# measure_temperature_sch.net
KiCad netlist of a schematic drawn in EAGLE
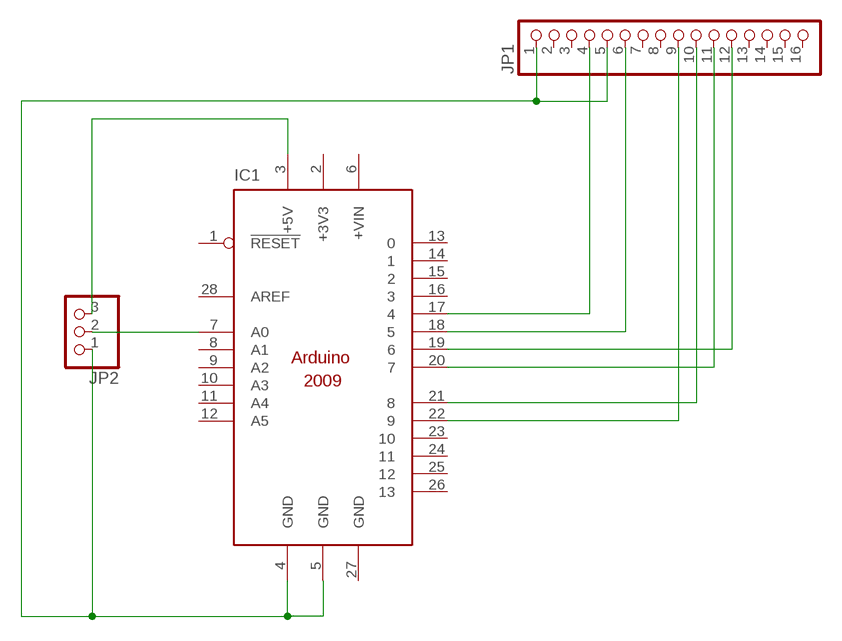
[diagram p0: schematic, sheet 1]

(export (version "E")
  (design (tool "Eeschema 10.0.6"))
  (components
    (comp (ref "IC1")
      (value "ARDUINO2009_12")
      (footprint "eagle-import:ARDUINO2009_2")
      (libsource (lib "eagle-import") (part "ARDUINO2009_12"))
    )
    (comp (ref "JP1")
      (value "PINHD-1X16")
      (footprint "eagle-import:1X16")
      (libsource (lib "eagle-import") (part "PINHD-1X16"))
    )
    (comp (ref "JP2")
      (value "PINHD-1X3")
      (footprint "eagle-import:1X03")
      (libsource (lib "eagle-import") (part "PINHD-1X3"))
    )
  )
  (nets
    (net (code "1") (name "/+3V3") (class "Default")
      (node (ref "IC1") (pin "2") (pinfunction "+3V3_2") (pintype "power_in"))
    )
    (net (code "2") (name "/GND") (class "Default")
      (node (ref "IC1") (pin "27") (pinfunction "GND_27") (pintype "power_in"))
    )
    (net (code "3") (name "Net-(IC1-+5V)") (class "Default")
      (node (ref "IC1") (pin "3") (pinfunction "+5V_3") (pintype "power_in"))
      (node (ref "JP2") (pin "3") (pinfunction "3_3") (pintype "passive"))
    )
    (net (code "4") (name "Net-(IC1-4)") (class "Default")
      (node (ref "IC1") (pin "17") (pinfunction "4_17") (pintype "bidirectional"))
      (node (ref "JP1") (pin "4") (pinfunction "4_4") (pintype "passive"))
    )
    (net (code "5") (name "Net-(IC1-5)") (class "Default")
      (node (ref "IC1") (pin "18") (pinfunction "5_18") (pintype "bidirectional"))
      (node (ref "JP1") (pin "6") (pinfunction "6_6") (pintype "passive"))
    )
    (net (code "6") (name "Net-(IC1-6)") (class "Default")
      (node (ref "IC1") (pin "19") (pinfunction "6_19") (pintype "bidirectional"))
      (node (ref "JP1") (pin "12") (pinfunction "12_12") (pintype "passive"))
    )
    (net (code "7") (name "Net-(IC1-7)") (class "Default")
      (node (ref "IC1") (pin "20") (pinfunction "7_20") (pintype "bidirectional"))
      (node (ref "JP1") (pin "11") (pinfunction "11_11") (pintype "passive"))
    )
    (net (code "8") (name "Net-(IC1-8)") (class "Default")
      (node (ref "IC1") (pin "21") (pinfunction "8_21") (pintype "bidirectional"))
      (node (ref "JP1") (pin "10") (pinfunction "10_10") (pintype "passive"))
    )
    (net (code "9") (name "Net-(IC1-9)") (class "Default")
      (node (ref "IC1") (pin "22") (pinfunction "9_22") (pintype "bidirectional"))
      (node (ref "JP1") (pin "9") (pinfunction "9_9") (pintype "passive"))
    )
    (net (code "10") (name "Net-(IC1-A0)") (class "Default")
      (node (ref "IC1") (pin "7") (pinfunction "A0_7") (pintype "bidirectional"))
      (node (ref "JP2") (pin "2") (pinfunction "2_2") (pintype "passive"))
    )
    (net (code "11") (name "Net-(IC1-GND-Pad4)") (class "Default")
      (node (ref "IC1") (pin "4") (pinfunction "GND_4") (pintype "power_in"))
      (node (ref "IC1") (pin "5") (pinfunction "GND_5") (pintype "power_in"))
      (node (ref "JP1") (pin "1") (pinfunction "1_1") (pintype "passive"))
      (node (ref "JP1") (pin "5") (pinfunction "5_5") (pintype "passive"))
      (node (ref "JP2") (pin "1") (pinfunction "1_1") (pintype "passive"))
    )
    (net (code "12") (name "unconnected-(IC1-+VIN-Pad6)") (class "Default")
      (node (ref "IC1") (pin "6") (pinfunction "+VIN_6") (pintype "bidirectional"))
    )
    (net (code "13") (name "unconnected-(IC1-0-Pad13)") (class "Default")
      (node (ref "IC1") (pin "13") (pinfunction "0_13") (pintype "bidirectional"))
    )
    (net (code "14") (name "unconnected-(IC1-1-Pad14)") (class "Default")
      (node (ref "IC1") (pin "14") (pinfunction "1_14") (pintype "bidirectional"))
    )
    (net (code "15") (name "unconnected-(IC1-2-Pad15)") (class "Default")
      (node (ref "IC1") (pin "15") (pinfunction "2_15") (pintype "bidirectional"))
    )
    (net (code "16") (name "unconnected-(IC1-3-Pad16)") (class "Default")
      (node (ref "IC1") (pin "16") (pinfunction "3_16") (pintype "bidirectional"))
    )
    (net (code "17") (name "unconnected-(IC1-10-Pad23)") (class "Default")
      (node (ref "IC1") (pin "23") (pinfunction "10_23") (pintype "bidirectional"))
    )
    (net (code "18") (name "unconnected-(IC1-11-Pad24)") (class "Default")
      (node (ref "IC1") (pin "24") (pinfunction "11_24") (pintype "bidirectional"))
    )
    (net (code "19") (name "unconnected-(IC1-12-Pad25)") (class "Default")
      (node (ref "IC1") (pin "25") (pinfunction "12_25") (pintype "bidirectional"))
    )
    (net (code "20") (name "unconnected-(IC1-13-Pad26)") (class "Default")
      (node (ref "IC1") (pin "26") (pinfunction "13_26") (pintype "bidirectional"))
    )
    (net (code "21") (name "unconnected-(IC1-A1-Pad8)") (class "Default")
      (node (ref "IC1") (pin "8") (pinfunction "A1_8") (pintype "bidirectional"))
    )
    (net (code "22") (name "unconnected-(IC1-A2-Pad9)") (class "Default")
      (node (ref "IC1") (pin "9") (pinfunction "A2_9") (pintype "bidirectional"))
    )
    (net (code "23") (name "unconnected-(IC1-A3-Pad10)") (class "Default")
      (node (ref "IC1") (pin "10") (pinfunction "A3_10") (pintype "bidirectional"))
    )
    (net (code "24") (name "unconnected-(IC1-A4-Pad11)") (class "Default")
      (node (ref "IC1") (pin "11") (pinfunction "A4_11") (pintype "bidirectional"))
    )
    (net (code "25") (name "unconnected-(IC1-A5-Pad12)") (class "Default")
      (node (ref "IC1") (pin "12") (pinfunction "A5_12") (pintype "bidirectional"))
    )
    (net (code "26") (name "unconnected-(IC1-AREF-Pad28)") (class "Default")
      (node (ref "IC1") (pin "28") (pinfunction "AREF_28") (pintype "bidirectional"))
    )
    (net (code "27") (name "unconnected-(IC1-~{RESET}-Pad1)") (class "Default")
      (node (ref "IC1") (pin "1") (pinfunction "~{RESET}_1") (pintype "bidirectional"))
    )
    (net (code "28") (name "unconnected-(JP1-Pad2)") (class "Default")
      (node (ref "JP1") (pin "2") (pinfunction "2_2") (pintype "passive"))
    )
    (net (code "29") (name "unconnected-(JP1-Pad3)") (class "Default")
      (node (ref "JP1") (pin "3") (pinfunction "3_3") (pintype "passive"))
    )
    (net (code "30") (name "unconnected-(JP1-Pad7)") (class "Default")
      (node (ref "JP1") (pin "7") (pinfunction "7_7") (pintype "passive"))
    )
    (net (code "31") (name "unconnected-(JP1-Pad8)") (class "Default")
      (node (ref "JP1") (pin "8") (pinfunction "8_8") (pintype "passive"))
    )
    (net (code "32") (name "unconnected-(JP1-Pad13)") (class "Default")
      (node (ref "JP1") (pin "13") (pinfunction "13_13") (pintype "passive"))
    )
    (net (code "33") (name "unconnected-(JP1-Pad14)") (class "Default")
      (node (ref "JP1") (pin "14") (pinfunction "14_14") (pintype "passive"))
    )
    (net (code "34") (name "unconnected-(JP1-Pad15)") (class "Default")
      (node (ref "JP1") (pin "15") (pinfunction "15_15") (pintype "passive"))
    )
    (net (code "35") (name "unconnected-(JP1-Pad16)") (class "Default")
      (node (ref "JP1") (pin "16") (pinfunction "16_16") (pintype "passive"))
    )
  )
)
